# relays-board.net
KiCad netlist of a schematic drawn in EAGLE
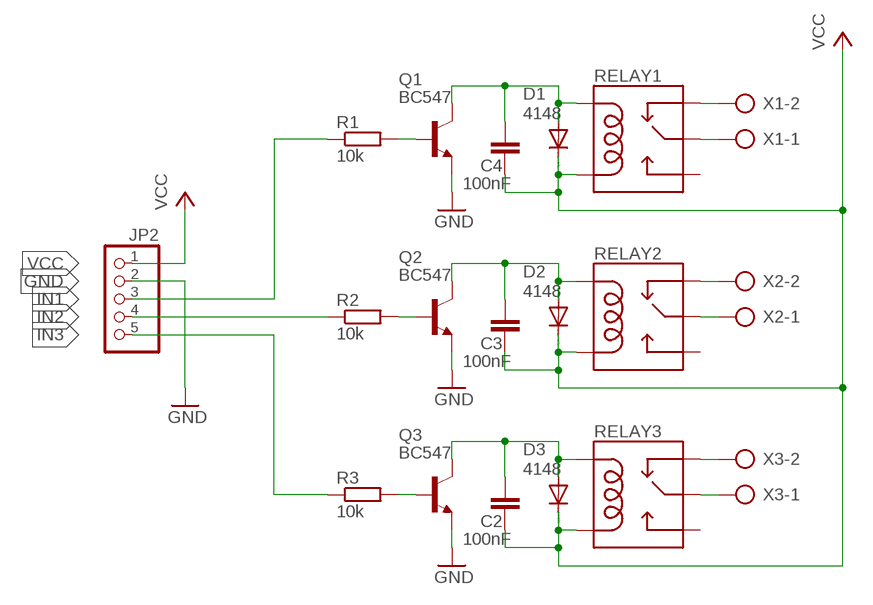
[diagram p0: schematic, sheet 1]

(export (version "E")
  (design (tool "Eeschema 10.0.6"))
  (components
    (comp (ref "C2")
      (value "100nF")
      (footprint "eagle-import:C025-025X050")
      (libsource (lib "eagle-import") (part "C-EU025-025X050"))
    )
    (comp (ref "C3")
      (value "100nF")
      (footprint "eagle-import:C025-025X050")
      (libsource (lib "eagle-import") (part "C-EU025-025X050"))
    )
    (comp (ref "C4")
      (value "100nF")
      (footprint "eagle-import:C025-025X050")
      (libsource (lib "eagle-import") (part "C-EU025-025X050"))
    )
    (comp (ref "D1")
      (value "4148")
      (footprint "eagle-import:DO35-10")
      (libsource (lib "eagle-import") (part "1N4148DO35-10"))
    )
    (comp (ref "D2")
      (value "4148")
      (footprint "eagle-import:DO35-10")
      (libsource (lib "eagle-import") (part "1N4148DO35-10"))
    )
    (comp (ref "D3")
      (value "4148")
      (footprint "eagle-import:DO35-10")
      (libsource (lib "eagle-import") (part "1N4148DO35-10"))
    )
    (comp (ref "JP2")
      (value "PINHD-1X5")
      (footprint "eagle-import:1X05")
      (libsource (lib "eagle-import") (part "PINHD-1X5"))
    )
    (comp (ref "Q1")
      (value "BC547")
      (footprint "eagle-import:TO92")
      (libsource (lib "eagle-import") (part "BC547"))
    )
    (comp (ref "Q2")
      (value "BC547")
      (footprint "eagle-import:TO92")
      (libsource (lib "eagle-import") (part "BC547"))
    )
    (comp (ref "Q3")
      (value "BC547")
      (footprint "eagle-import:TO92")
      (libsource (lib "eagle-import") (part "BC547"))
    )
    (comp (ref "R1")
      (value "10k")
      (footprint "eagle-import:0207_10")
      (libsource (lib "eagle-import") (part "R-EU_0207/10"))
    )
    (comp (ref "R2")
      (value "10k")
      (footprint "eagle-import:0207_10")
      (libsource (lib "eagle-import") (part "R-EU_0207/10"))
    )
    (comp (ref "R3")
      (value "10k")
      (footprint "eagle-import:0207_10")
      (libsource (lib "eagle-import") (part "R-EU_0207/10"))
    )
    (comp (ref "RELAY1")
      (value "RELAYPTH")
      (footprint "eagle-import:SRD-05VDC-SL-C")
      (libsource (lib "eagle-import") (part "RELAYPTH"))
    )
    (comp (ref "RELAY2")
      (value "RELAYPTH")
      (footprint "eagle-import:SRD-05VDC-SL-C")
      (libsource (lib "eagle-import") (part "RELAYPTH"))
    )
    (comp (ref "RELAY3")
      (value "RELAYPTH")
      (footprint "eagle-import:SRD-05VDC-SL-C")
      (libsource (lib "eagle-import") (part "RELAYPTH"))
    )
    (comp (ref "X1")
      (value "AK300/2")
      (footprint "eagle-import:AK300_2")
      (libsource (lib "eagle-import") (part "AK300/2"))
    )
    (comp (ref "X2")
      (value "AK300/2")
      (footprint "eagle-import:AK300_2")
      (libsource (lib "eagle-import") (part "AK300/2"))
    )
    (comp (ref "X3")
      (value "AK300/2")
      (footprint "eagle-import:AK300_2")
      (libsource (lib "eagle-import") (part "AK300/2"))
    )
  )
  (nets
    (net (code "1") (name "GND") (class "Default")
      (node (ref "JP2") (pin "2") (pinfunction "2_2") (pintype "passive"))
      (node (ref "Q1") (pin "1") (pinfunction "E_1") (pintype "passive"))
      (node (ref "Q2") (pin "1") (pinfunction "E_1") (pintype "passive"))
      (node (ref "Q3") (pin "1") (pinfunction "E_1") (pintype "passive"))
    )
    (net (code "2") (name "IN1") (class "Default")
      (node (ref "JP2") (pin "3") (pinfunction "3_3") (pintype "passive"))
      (node (ref "R1") (pin "1") (pinfunction "1_1") (pintype "passive"))
    )
    (net (code "3") (name "IN2") (class "Default")
      (node (ref "JP2") (pin "4") (pinfunction "4_4") (pintype "passive"))
      (node (ref "R2") (pin "1") (pinfunction "1_1") (pintype "passive"))
    )
    (net (code "4") (name "IN3") (class "Default")
      (node (ref "JP2") (pin "5") (pinfunction "5_5") (pintype "passive"))
      (node (ref "R3") (pin "1") (pinfunction "1_1") (pintype "passive"))
    )
    (net (code "5") (name "Net-(Q1-B)") (class "Default")
      (node (ref "Q1") (pin "2") (pinfunction "B_2") (pintype "passive"))
      (node (ref "R1") (pin "2") (pinfunction "2_2") (pintype "passive"))
    )
    (net (code "6") (name "Net-(Q1-C)") (class "Default")
      (node (ref "C4") (pin "1") (pinfunction "1_1") (pintype "passive"))
      (node (ref "D1") (pin "A") (pinfunction "A_A") (pintype "passive"))
      (node (ref "Q1") (pin "3") (pinfunction "C_3") (pintype "passive"))
      (node (ref "RELAY1") (pin "COIL1") (pinfunction "COIL1_COIL1") (pintype "bidirectional"))
    )
    (net (code "7") (name "Net-(Q2-B)") (class "Default")
      (node (ref "Q2") (pin "2") (pinfunction "B_2") (pintype "passive"))
      (node (ref "R2") (pin "2") (pinfunction "2_2") (pintype "passive"))
    )
    (net (code "8") (name "Net-(Q2-C)") (class "Default")
      (node (ref "C3") (pin "1") (pinfunction "1_1") (pintype "passive"))
      (node (ref "D2") (pin "A") (pinfunction "A_A") (pintype "passive"))
      (node (ref "Q2") (pin "3") (pinfunction "C_3") (pintype "passive"))
      (node (ref "RELAY2") (pin "COIL1") (pinfunction "COIL1_COIL1") (pintype "bidirectional"))
    )
    (net (code "9") (name "Net-(Q3-B)") (class "Default")
      (node (ref "Q3") (pin "2") (pinfunction "B_2") (pintype "passive"))
      (node (ref "R3") (pin "2") (pinfunction "2_2") (pintype "passive"))
    )
    (net (code "10") (name "Net-(Q3-C)") (class "Default")
      (node (ref "C2") (pin "1") (pinfunction "1_1") (pintype "passive"))
      (node (ref "D3") (pin "A") (pinfunction "A_A") (pintype "passive"))
      (node (ref "Q3") (pin "3") (pinfunction "C_3") (pintype "passive"))
      (node (ref "RELAY3") (pin "COIL1") (pinfunction "COIL1_COIL1") (pintype "bidirectional"))
    )
    (net (code "11") (name "Net-(RELAY1-SWCLOSE)") (class "Default")
      (node (ref "RELAY1") (pin "SWCLOSED") (pinfunction "SWCLOSE_SWCLOSED") (pintype "bidirectional"))
      (node (ref "X1") (pin "2") (pinfunction "KL_2") (pintype "passive"))
    )
    (net (code "12") (name "Net-(RELAY2-SWCLOSE)") (class "Default")
      (node (ref "RELAY2") (pin "SWCLOSED") (pinfunction "SWCLOSE_SWCLOSED") (pintype "bidirectional"))
      (node (ref "X2") (pin "2") (pinfunction "KL_2") (pintype "passive"))
    )
    (net (code "13") (name "Net-(RELAY3-SWCLOSE)") (class "Default")
      (node (ref "RELAY3") (pin "SWCLOSED") (pinfunction "SWCLOSE_SWCLOSED") (pintype "bidirectional"))
      (node (ref "X3") (pin "2") (pinfunction "KL_2") (pintype "passive"))
    )
    (net (code "14") (name "Net-(X1A-KL)") (class "Default")
      (node (ref "RELAY1") (pin "SWCOMMON") (pinfunction "SWCOMMON_SWCOMMON") (pintype "bidirectional"))
      (node (ref "X1") (pin "1") (pinfunction "KL_1") (pintype "passive"))
    )
    (net (code "15") (name "Net-(X2A-KL)") (class "Default")
      (node (ref "RELAY2") (pin "SWCOMMON") (pinfunction "SWCOMMON_SWCOMMON") (pintype "bidirectional"))
      (node (ref "X2") (pin "1") (pinfunction "KL_1") (pintype "passive"))
    )
    (net (code "16") (name "Net-(X3A-KL)") (class "Default")
      (node (ref "RELAY3") (pin "SWCOMMON") (pinfunction "SWCOMMON_SWCOMMON") (pintype "bidirectional"))
      (node (ref "X3") (pin "1") (pinfunction "KL_1") (pintype "passive"))
    )
    (net (code "17") (name "VCC") (class "Default")
      (node (ref "C2") (pin "2") (pinfunction "2_2") (pintype "passive"))
      (node (ref "C3") (pin "2") (pinfunction "2_2") (pintype "passive"))
      (node (ref "C4") (pin "2") (pinfunction "2_2") (pintype "passive"))
      (node (ref "D1") (pin "C") (pinfunction "C_C") (pintype "passive"))
      (node (ref "D2") (pin "C") (pinfunction "C_C") (pintype "passive"))
      (node (ref "D3") (pin "C") (pinfunction "C_C") (pintype "passive"))
      (node (ref "JP2") (pin "1") (pinfunction "1_1") (pintype "passive"))
      (node (ref "RELAY1") (pin "COIL0") (pinfunction "COIL0_COIL0") (pintype "bidirectional"))
      (node (ref "RELAY2") (pin "COIL0") (pinfunction "COIL0_COIL0") (pintype "bidirectional"))
      (node (ref "RELAY3") (pin "COIL0") (pinfunction "COIL0_COIL0") (pintype "bidirectional"))
    )
    (net (code "18") (name "unconnected-(RELAY1-PadSWOPEN)") (class "Default")
      (node (ref "RELAY1") (pin "SWOPEN") (pinfunction "SWOPEN_SWOPEN") (pintype "bidirectional"))
    )
    (net (code "19") (name "unconnected-(RELAY2-PadSWOPEN)") (class "Default")
      (node (ref "RELAY2") (pin "SWOPEN") (pinfunction "SWOPEN_SWOPEN") (pintype "bidirectional"))
    )
    (net (code "20") (name "unconnected-(RELAY3-PadSWOPEN)") (class "Default")
      (node (ref "RELAY3") (pin "SWOPEN") (pinfunction "SWOPEN_SWOPEN") (pintype "bidirectional"))
    )
  )
)
